# Control.net
KiCad netlist of a schematic drawn in EAGLE
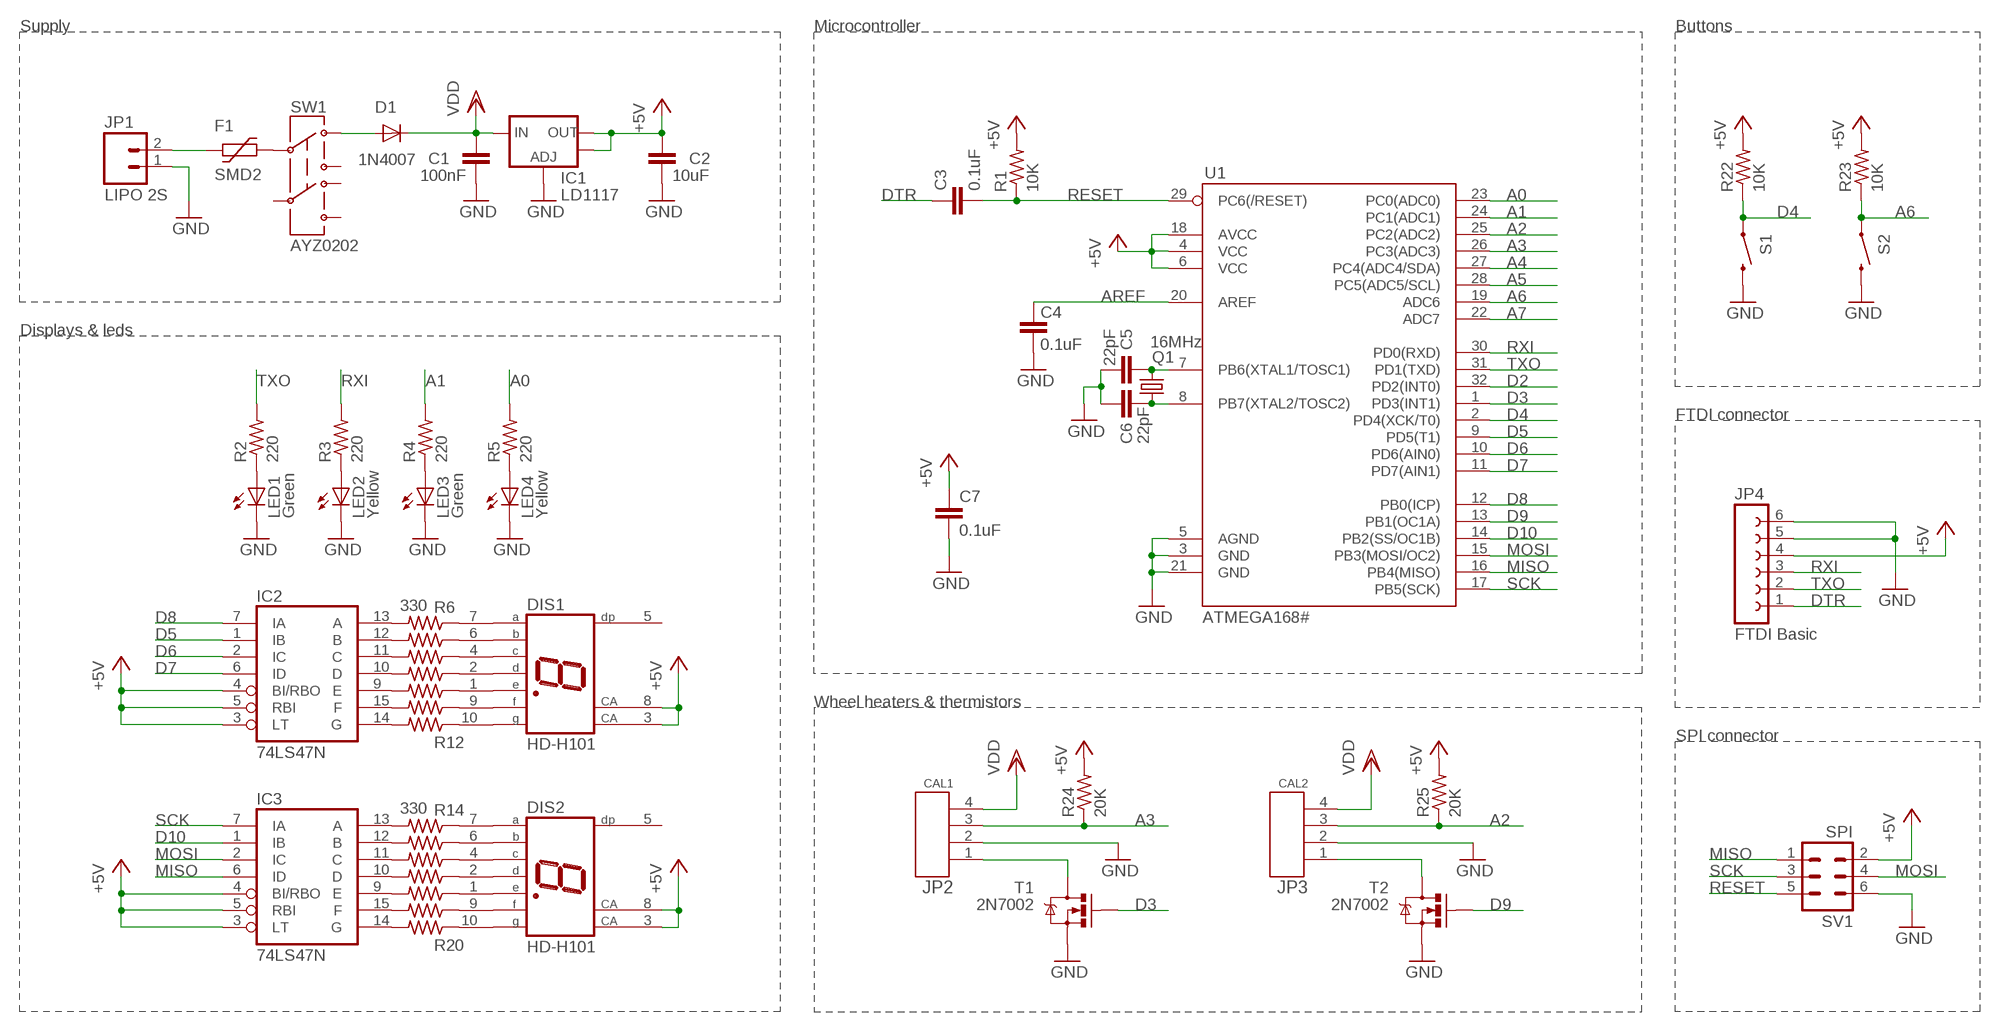
[diagram p0: schematic, sheet 1]

(export (version "E")
  (design (tool "Eeschema 10.0.6"))
  (components
    (comp (ref "C1")
      (value "100nF")
      (footprint "eagle-import:C0805")
      (libsource (lib "eagle-import") (part "C-EUC0805"))
    )
    (comp (ref "C2")
      (value "10uF")
      (footprint "eagle-import:C0805")
      (libsource (lib "eagle-import") (part "C-EUC0805"))
    )
    (comp (ref "C3")
      (value "0.1uF")
      (footprint "eagle-import:C0805")
      (libsource (lib "eagle-import") (part "C-EUC0805"))
    )
    (comp (ref "C4")
      (value "0.1uF")
      (footprint "eagle-import:C0805")
      (libsource (lib "eagle-import") (part "C-EUC0805"))
    )
    (comp (ref "C5")
      (value "22pF")
      (footprint "eagle-import:C0805")
      (libsource (lib "eagle-import") (part "C-EUC0805"))
    )
    (comp (ref "C6")
      (value "22pF")
      (footprint "eagle-import:C0805")
      (libsource (lib "eagle-import") (part "C-EUC0805"))
    )
    (comp (ref "C7")
      (value "0.1uF")
      (footprint "eagle-import:C0805")
      (libsource (lib "eagle-import") (part "C-EUC0805"))
    )
    (comp (ref "D1")
      (value "1N4007")
      (footprint "eagle-import:SOD106-R")
      (libsource (lib "eagle-import") (part "DIODE-SOD106-R"))
    )
    (comp (ref "DIS1")
      (value "HD-H101")
      (footprint "eagle-import:HDSP-M")
      (libsource (lib "eagle-import") (part "HD-H101"))
    )
    (comp (ref "DIS2")
      (value "HD-H101")
      (footprint "eagle-import:HDSP-M")
      (fields (field (name "OC_FARNELL") "unknown") (field (name "OC_NEWARK") "unknown"))
      (libsource (lib "eagle-import") (part "HD-H101"))
    )
    (comp (ref "F1")
      (value "SMD2")
      (footprint "eagle-import:SMD2")
      (libsource (lib "eagle-import") (part "SMD2"))
    )
    (comp (ref "IC1")
      (value "LD1117")
      (footprint "eagle-import:SOT223")
      (libsource (lib "eagle-import") (part "V_REG_LM1117SOT223"))
    )
    (comp (ref "IC2")
      (value "74LS47N")
      (footprint "eagle-import:DIL16")
      (libsource (lib "eagle-import") (part "7447NLS"))
    )
    (comp (ref "IC3")
      (value "74LS47N")
      (footprint "eagle-import:DIL16")
      (libsource (lib "eagle-import") (part "7447NLS"))
    )
    (comp (ref "JP1")
      (value "LIPO 2S")
      (footprint "eagle-import:1X02")
      (libsource (lib "eagle-import") (part "M02NG"))
    )
    (comp (ref "JP2")
      (value "CAL1")
      (footprint "eagle-import:4_PINES_MACHO_TUMBADOS")
      (libsource (lib "eagle-import") (part "4_PINES_RA"))
    )
    (comp (ref "JP3")
      (value "CAL2")
      (footprint "eagle-import:4_PINES_MACHO_TUMBADOS")
      (libsource (lib "eagle-import") (part "4_PINES_RA"))
    )
    (comp (ref "JP4")
      (value "FTDI Basic")
      (footprint "eagle-import:FE06W")
      (libsource (lib "eagle-import") (part "FE06W"))
    )
    (comp (ref "LED1")
      (value "Green")
      (footprint "eagle-import:LED3MM")
      (libsource (lib "eagle-import") (part "LED3MM"))
    )
    (comp (ref "LED2")
      (value "Yellow")
      (footprint "eagle-import:LED3MM")
      (libsource (lib "eagle-import") (part "LED3MM"))
    )
    (comp (ref "LED3")
      (value "Green")
      (footprint "eagle-import:LED3MM")
      (libsource (lib "eagle-import") (part "LED3MM"))
    )
    (comp (ref "LED4")
      (value "Yellow")
      (footprint "eagle-import:LED3MM")
      (libsource (lib "eagle-import") (part "LED3MM"))
    )
    (comp (ref "Q1")
      (value "16MHz")
      (footprint "eagle-import:HC49_S")
      (libsource (lib "eagle-import") (part "CRYSTALHC49S"))
    )
    (comp (ref "R1")
      (value "10K")
      (footprint "eagle-import:R0805")
      (libsource (lib "eagle-import") (part "R-US_R0805"))
    )
    (comp (ref "R2")
      (value "220")
      (footprint "eagle-import:R0805")
      (libsource (lib "eagle-import") (part "R-US_R0805"))
    )
    (comp (ref "R3")
      (value "220")
      (footprint "eagle-import:R0805")
      (libsource (lib "eagle-import") (part "R-US_R0805"))
    )
    (comp (ref "R4")
      (value "220")
      (footprint "eagle-import:R0805")
      (libsource (lib "eagle-import") (part "R-US_R0805"))
    )
    (comp (ref "R5")
      (value "220")
      (footprint "eagle-import:R0805")
      (libsource (lib "eagle-import") (part "R-US_R0805"))
    )
    (comp (ref "R6")
      (value "330")
      (footprint "eagle-import:R0805")
      (libsource (lib "eagle-import") (part "R-US_R0805"))
    )
    (comp (ref "R7")
      (value "330")
      (footprint "eagle-import:R0805")
      (libsource (lib "eagle-import") (part "R-US_R0805"))
    )
    (comp (ref "R8")
      (value "330")
      (footprint "eagle-import:R0805")
      (libsource (lib "eagle-import") (part "R-US_R0805"))
    )
    (comp (ref "R9")
      (value "330")
      (footprint "eagle-import:R0805")
      (libsource (lib "eagle-import") (part "R-US_R0805"))
    )
    (comp (ref "R10")
      (value "330")
      (footprint "eagle-import:R0805")
      (libsource (lib "eagle-import") (part "R-US_R0805"))
    )
    (comp (ref "R11")
      (value "330")
      (footprint "eagle-import:R0805")
      (libsource (lib "eagle-import") (part "R-US_R0805"))
    )
    (comp (ref "R12")
      (value "330")
      (footprint "eagle-import:R0805")
      (libsource (lib "eagle-import") (part "R-US_R0805"))
    )
    (comp (ref "R14")
      (value "330")
      (footprint "eagle-import:R0805")
      (libsource (lib "eagle-import") (part "R-US_R0805"))
    )
    (comp (ref "R15")
      (value "330")
      (footprint "eagle-import:R0805")
      (libsource (lib "eagle-import") (part "R-US_R0805"))
    )
    (comp (ref "R16")
      (value "330")
      (footprint "eagle-import:R0805")
      (libsource (lib "eagle-import") (part "R-US_R0805"))
    )
    (comp (ref "R17")
      (value "330")
      (footprint "eagle-import:R0805")
      (libsource (lib "eagle-import") (part "R-US_R0805"))
    )
    (comp (ref "R18")
      (value "330")
      (footprint "eagle-import:R0805")
      (libsource (lib "eagle-import") (part "R-US_R0805"))
    )
    (comp (ref "R19")
      (value "330")
      (footprint "eagle-import:R0805")
      (libsource (lib "eagle-import") (part "R-US_R0805"))
    )
    (comp (ref "R20")
      (value "330")
      (footprint "eagle-import:R0805")
      (libsource (lib "eagle-import") (part "R-US_R0805"))
    )
    (comp (ref "R22")
      (value "10K")
      (footprint "eagle-import:R0805")
      (libsource (lib "eagle-import") (part "R-US_R0805"))
    )
    (comp (ref "R23")
      (value "10K")
      (footprint "eagle-import:R0805")
      (libsource (lib "eagle-import") (part "R-US_R0805"))
    )
    (comp (ref "R24")
      (value "20K")
      (footprint "eagle-import:R0805")
      (libsource (lib "eagle-import") (part "R-US_R0805"))
    )
    (comp (ref "R25")
      (value "20K")
      (footprint "eagle-import:R0805")
      (libsource (lib "eagle-import") (part "R-US_R0805"))
    )
    (comp (ref "S1")
      (value "SWITCH-MOMENTARY-2PTH")
      (footprint "eagle-import:TACTILE-PTH")
      (libsource (lib "eagle-import") (part "SWITCH-MOMENTARY-2PTH"))
    )
    (comp (ref "S2")
      (value "SWITCH-MOMENTARY-2PTH")
      (footprint "eagle-import:TACTILE-PTH")
      (libsource (lib "eagle-import") (part "SWITCH-MOMENTARY-2PTH"))
    )
    (comp (ref "SV1")
      (value "SPI")
      (footprint "eagle-import:MA03-2")
      (libsource (lib "eagle-import") (part "MA03-2"))
    )
    (comp (ref "SW1")
      (value "AYZ0202")
      (footprint "eagle-import:AYZ0202")
      (libsource (lib "eagle-import") (part "AYZ0202"))
    )
    (comp (ref "T1")
      (value "2N7002")
      (footprint "eagle-import:SOT23-3")
      (libsource (lib "eagle-import") (part "MOSFET-NCHANNELSMD"))
    )
    (comp (ref "T2")
      (value "2N7002")
      (footprint "eagle-import:SOT23-3")
      (libsource (lib "eagle-import") (part "MOSFET-NCHANNELSMD"))
    )
    (comp (ref "U1")
      (value "ATMEGA168#")
      (footprint "eagle-import:TQFP32-08")
      (libsource (lib "eagle-import") (part "ATMEGA168"))
    )
  )
  (nets
    (net (code "1") (name "+5V") (class "Default")
      (node (ref "C2") (pin "1") (pinfunction "1_1") (pintype "passive"))
      (node (ref "C7") (pin "1") (pinfunction "1_1") (pintype "passive"))
      (node (ref "DIS1") (pin "3") (pinfunction "CA_3") (pintype "passive"))
      (node (ref "DIS1") (pin "8") (pinfunction "CA_8") (pintype "passive"))
      (node (ref "DIS2") (pin "3") (pinfunction "CA_3") (pintype "passive"))
      (node (ref "DIS2") (pin "8") (pinfunction "CA_8") (pintype "passive"))
      (node (ref "IC1") (pin "2") (pinfunction "OUT_2") (pintype "output"))
      (node (ref "IC1") (pin "4") (pinfunction "OUT_4") (pintype "output"))
      (node (ref "IC2") (pin "3") (pinfunction "LT_3") (pintype "input"))
      (node (ref "IC2") (pin "4") (pinfunction "BI/RBO_4") (pintype "input"))
      (node (ref "IC2") (pin "5") (pinfunction "RBI_5") (pintype "input"))
      (node (ref "IC3") (pin "3") (pinfunction "LT_3") (pintype "input"))
      (node (ref "IC3") (pin "4") (pinfunction "BI/RBO_4") (pintype "input"))
      (node (ref "IC3") (pin "5") (pinfunction "RBI_5") (pintype "input"))
      (node (ref "JP4") (pin "4") (pinfunction "4_4") (pintype "passive"))
      (node (ref "R1") (pin "2") (pinfunction "2_2") (pintype "passive"))
      (node (ref "R22") (pin "2") (pinfunction "2_2") (pintype "passive"))
      (node (ref "R23") (pin "2") (pinfunction "2_2") (pintype "passive"))
      (node (ref "R24") (pin "2") (pinfunction "2_2") (pintype "passive"))
      (node (ref "R25") (pin "2") (pinfunction "2_2") (pintype "passive"))
      (node (ref "SV1") (pin "2") (pinfunction "2_2") (pintype "passive"))
      (node (ref "U1") (pin "18") (pinfunction "AVCC_18") (pintype "bidirectional"))
      (node (ref "U1") (pin "4") (pinfunction "VCC_4") (pintype "bidirectional"))
      (node (ref "U1") (pin "6") (pinfunction "VCC_6") (pintype "bidirectional"))
    )
    (net (code "2") (name "/A0") (class "Default")
      (node (ref "R5") (pin "2") (pinfunction "2_2") (pintype "passive"))
      (node (ref "U1") (pin "23") (pinfunction "PC0(ADC0)_23") (pintype "bidirectional"))
    )
    (net (code "3") (name "/A1") (class "Default")
      (node (ref "R4") (pin "2") (pinfunction "2_2") (pintype "passive"))
      (node (ref "U1") (pin "24") (pinfunction "PC1(ADC1)_24") (pintype "bidirectional"))
    )
    (net (code "4") (name "/A2") (class "Default")
      (node (ref "JP3") (pin "3") (pinfunction "3_3") (pintype "bidirectional"))
      (node (ref "R25") (pin "1") (pinfunction "1_1") (pintype "passive"))
      (node (ref "U1") (pin "25") (pinfunction "PC2(ADC2)_25") (pintype "bidirectional"))
    )
    (net (code "5") (name "/A3") (class "Default")
      (node (ref "JP2") (pin "3") (pinfunction "3_3") (pintype "bidirectional"))
      (node (ref "R24") (pin "1") (pinfunction "1_1") (pintype "passive"))
      (node (ref "U1") (pin "26") (pinfunction "PC3(ADC3)_26") (pintype "bidirectional"))
    )
    (net (code "6") (name "/A4") (class "Default")
      (node (ref "U1") (pin "27") (pinfunction "PC4(ADC4/SDA)_27") (pintype "bidirectional"))
    )
    (net (code "7") (name "/A5") (class "Default")
      (node (ref "U1") (pin "28") (pinfunction "PC5(ADC5/SCL)_28") (pintype "bidirectional"))
    )
    (net (code "8") (name "/A6") (class "Default")
      (node (ref "R23") (pin "1") (pinfunction "1_1") (pintype "passive"))
      (node (ref "S2") (pin "1") (pinfunction "1_1") (pintype "passive"))
      (node (ref "U1") (pin "19") (pinfunction "ADC6_19") (pintype "bidirectional"))
    )
    (net (code "9") (name "/A7") (class "Default")
      (node (ref "U1") (pin "22") (pinfunction "ADC7_22") (pintype "bidirectional"))
    )
    (net (code "10") (name "/AREF") (class "Default")
      (node (ref "C4") (pin "2") (pinfunction "2_2") (pintype "passive"))
      (node (ref "U1") (pin "20") (pinfunction "AREF_20") (pintype "bidirectional"))
    )
    (net (code "11") (name "/D2") (class "Default")
      (node (ref "U1") (pin "32") (pinfunction "PD2(INT0)_32") (pintype "bidirectional"))
    )
    (net (code "12") (name "/D3") (class "Default")
      (node (ref "T1") (pin "1") (pinfunction "G_1") (pintype "passive"))
      (node (ref "U1") (pin "1") (pinfunction "PD3(INT1)_1") (pintype "bidirectional"))
    )
    (net (code "13") (name "/D4") (class "Default")
      (node (ref "R22") (pin "1") (pinfunction "1_1") (pintype "passive"))
      (node (ref "S1") (pin "1") (pinfunction "1_1") (pintype "passive"))
      (node (ref "U1") (pin "2") (pinfunction "PD4(XCK/T0)_2") (pintype "bidirectional"))
    )
    (net (code "14") (name "/D5") (class "Default")
      (node (ref "IC2") (pin "1") (pinfunction "IB_1") (pintype "input"))
      (node (ref "U1") (pin "9") (pinfunction "PD5(T1)_9") (pintype "bidirectional"))
    )
    (net (code "15") (name "/D6") (class "Default")
      (node (ref "IC2") (pin "2") (pinfunction "IC_2") (pintype "input"))
      (node (ref "U1") (pin "10") (pinfunction "PD6(AIN0)_10") (pintype "bidirectional"))
    )
    (net (code "16") (name "/D7") (class "Default")
      (node (ref "IC2") (pin "6") (pinfunction "ID_6") (pintype "input"))
      (node (ref "U1") (pin "11") (pinfunction "PD7(AIN1)_11") (pintype "bidirectional"))
    )
    (net (code "17") (name "/D8") (class "Default")
      (node (ref "IC2") (pin "7") (pinfunction "IA_7") (pintype "input"))
      (node (ref "U1") (pin "12") (pinfunction "PB0(ICP)_12") (pintype "bidirectional"))
    )
    (net (code "18") (name "/D9") (class "Default")
      (node (ref "T2") (pin "1") (pinfunction "G_1") (pintype "passive"))
      (node (ref "U1") (pin "13") (pinfunction "PB1(OC1A)_13") (pintype "bidirectional"))
    )
    (net (code "19") (name "/D10") (class "Default")
      (node (ref "IC3") (pin "1") (pinfunction "IB_1") (pintype "input"))
      (node (ref "U1") (pin "14") (pinfunction "PB2(SS/OC1B)_14") (pintype "bidirectional"))
    )
    (net (code "20") (name "/DTR") (class "Default")
      (node (ref "C3") (pin "1") (pinfunction "1_1") (pintype "passive"))
      (node (ref "JP4") (pin "1") (pinfunction "1_1") (pintype "passive"))
    )
    (net (code "21") (name "/MISO") (class "Default")
      (node (ref "IC3") (pin "6") (pinfunction "ID_6") (pintype "input"))
      (node (ref "SV1") (pin "1") (pinfunction "1_1") (pintype "passive"))
      (node (ref "U1") (pin "16") (pinfunction "PB4(MISO)_16") (pintype "bidirectional"))
    )
    (net (code "22") (name "/MOSI") (class "Default")
      (node (ref "IC3") (pin "2") (pinfunction "IC_2") (pintype "input"))
      (node (ref "SV1") (pin "4") (pinfunction "4_4") (pintype "passive"))
      (node (ref "U1") (pin "15") (pinfunction "PB3(MOSI/OC2)_15") (pintype "bidirectional"))
    )
    (net (code "23") (name "/RESET") (class "Default")
      (node (ref "C3") (pin "2") (pinfunction "2_2") (pintype "passive"))
      (node (ref "R1") (pin "1") (pinfunction "1_1") (pintype "passive"))
      (node (ref "SV1") (pin "5") (pinfunction "5_5") (pintype "passive"))
      (node (ref "U1") (pin "29") (pinfunction "PC6(/RESET)_29") (pintype "bidirectional"))
    )
    (net (code "24") (name "/RXI") (class "Default")
      (node (ref "JP4") (pin "3") (pinfunction "3_3") (pintype "passive"))
      (node (ref "R3") (pin "2") (pinfunction "2_2") (pintype "passive"))
      (node (ref "U1") (pin "30") (pinfunction "PD0(RXD)_30") (pintype "bidirectional"))
    )
    (net (code "25") (name "/SCK") (class "Default")
      (node (ref "IC3") (pin "7") (pinfunction "IA_7") (pintype "input"))
      (node (ref "SV1") (pin "3") (pinfunction "3_3") (pintype "passive"))
      (node (ref "U1") (pin "17") (pinfunction "PB5(SCK)_17") (pintype "bidirectional"))
    )
    (net (code "26") (name "/TXO") (class "Default")
      (node (ref "JP4") (pin "2") (pinfunction "2_2") (pintype "passive"))
      (node (ref "R2") (pin "2") (pinfunction "2_2") (pintype "passive"))
      (node (ref "U1") (pin "31") (pinfunction "PD1(TXD)_31") (pintype "bidirectional"))
    )
    (net (code "27") (name "GND") (class "Default")
      (node (ref "C1") (pin "1") (pinfunction "1_1") (pintype "passive"))
      (node (ref "C2") (pin "2") (pinfunction "2_2") (pintype "passive"))
      (node (ref "C4") (pin "1") (pinfunction "1_1") (pintype "passive"))
      (node (ref "C5") (pin "1") (pinfunction "1_1") (pintype "passive"))
      (node (ref "C6") (pin "1") (pinfunction "1_1") (pintype "passive"))
      (node (ref "C7") (pin "2") (pinfunction "2_2") (pintype "passive"))
      (node (ref "IC1") (pin "1") (pinfunction "ADJ_1") (pintype "input"))
      (node (ref "JP1") (pin "1") (pinfunction "1_1") (pintype "passive"))
      (node (ref "JP2") (pin "2") (pinfunction "2_2") (pintype "bidirectional"))
      (node (ref "JP3") (pin "2") (pinfunction "2_2") (pintype "bidirectional"))
      (node (ref "JP4") (pin "5") (pinfunction "5_5") (pintype "passive"))
      (node (ref "JP4") (pin "6") (pinfunction "6_6") (pintype "passive"))
      (node (ref "LED1") (pin "K") (pinfunction "C_K") (pintype "passive"))
      (node (ref "LED2") (pin "K") (pinfunction "C_K") (pintype "passive"))
      (node (ref "LED3") (pin "K") (pinfunction "C_K") (pintype "passive"))
      (node (ref "LED4") (pin "K") (pinfunction "C_K") (pintype "passive"))
      (node (ref "S1") (pin "3") (pinfunction "2_3") (pintype "passive"))
      (node (ref "S2") (pin "3") (pinfunction "2_3") (pintype "passive"))
      (node (ref "SV1") (pin "6") (pinfunction "6_6") (pintype "passive"))
      (node (ref "T1") (pin "2") (pinfunction "S_2") (pintype "passive"))
      (node (ref "T2") (pin "2") (pinfunction "S_2") (pintype "passive"))
      (node (ref "U1") (pin "21") (pinfunction "GND_21") (pintype "bidirectional"))
      (node (ref "U1") (pin "3") (pinfunction "GND_3") (pintype "bidirectional"))
      (node (ref "U1") (pin "5") (pinfunction "AGND_5") (pintype "bidirectional"))
    )
    (net (code "28") (name "Net-(DIS1-A)") (class "Default")
      (node (ref "DIS1") (pin "7") (pinfunction "A_7") (pintype "passive"))
      (node (ref "R6") (pin "1") (pinfunction "1_1") (pintype "passive"))
    )
    (net (code "29") (name "Net-(DIS1-B)") (class "Default")
      (node (ref "DIS1") (pin "6") (pinfunction "B_6") (pintype "passive"))
      (node (ref "R7") (pin "1") (pinfunction "1_1") (pintype "passive"))
    )
    (net (code "30") (name "Net-(DIS1-C)") (class "Default")
      (node (ref "DIS1") (pin "4") (pinfunction "C_4") (pintype "passive"))
      (node (ref "R8") (pin "1") (pinfunction "1_1") (pintype "passive"))
    )
    (net (code "31") (name "Net-(DIS1-D)") (class "Default")
      (node (ref "DIS1") (pin "2") (pinfunction "D_2") (pintype "passive"))
      (node (ref "R9") (pin "1") (pinfunction "1_1") (pintype "passive"))
    )
    (net (code "32") (name "Net-(DIS1-E)") (class "Default")
      (node (ref "DIS1") (pin "1") (pinfunction "E_1") (pintype "passive"))
      (node (ref "R10") (pin "1") (pinfunction "1_1") (pintype "passive"))
    )
    (net (code "33") (name "Net-(DIS1-F)") (class "Default")
      (node (ref "DIS1") (pin "9") (pinfunction "F_9") (pintype "passive"))
      (node (ref "R11") (pin "1") (pinfunction "1_1") (pintype "passive"))
    )
    (net (code "34") (name "Net-(DIS1-G)") (class "Default")
      (node (ref "DIS1") (pin "10") (pinfunction "G_10") (pintype "passive"))
      (node (ref "R12") (pin "1") (pinfunction "1_1") (pintype "passive"))
    )
    (net (code "35") (name "Net-(DIS2-A)") (class "Default")
      (node (ref "DIS2") (pin "7") (pinfunction "A_7") (pintype "passive"))
      (node (ref "R14") (pin "1") (pinfunction "1_1") (pintype "passive"))
    )
    (net (code "36") (name "Net-(DIS2-B)") (class "Default")
      (node (ref "DIS2") (pin "6") (pinfunction "B_6") (pintype "passive"))
      (node (ref "R15") (pin "1") (pinfunction "1_1") (pintype "passive"))
    )
    (net (code "37") (name "Net-(DIS2-C)") (class "Default")
      (node (ref "DIS2") (pin "4") (pinfunction "C_4") (pintype "passive"))
      (node (ref "R16") (pin "1") (pinfunction "1_1") (pintype "passive"))
    )
    (net (code "38") (name "Net-(DIS2-D)") (class "Default")
      (node (ref "DIS2") (pin "2") (pinfunction "D_2") (pintype "passive"))
      (node (ref "R17") (pin "1") (pinfunction "1_1") (pintype "passive"))
    )
    (net (code "39") (name "Net-(DIS2-E)") (class "Default")
      (node (ref "DIS2") (pin "1") (pinfunction "E_1") (pintype "passive"))
      (node (ref "R18") (pin "1") (pinfunction "1_1") (pintype "passive"))
    )
    (net (code "40") (name "Net-(DIS2-F)") (class "Default")
      (node (ref "DIS2") (pin "9") (pinfunction "F_9") (pintype "passive"))
      (node (ref "R19") (pin "1") (pinfunction "1_1") (pintype "passive"))
    )
    (net (code "41") (name "Net-(DIS2-G)") (class "Default")
      (node (ref "DIS2") (pin "10") (pinfunction "G_10") (pintype "passive"))
      (node (ref "R20") (pin "1") (pinfunction "1_1") (pintype "passive"))
    )
    (net (code "42") (name "Net-(F1-1)") (class "Default")
      (node (ref "F1") (pin "P$1") (pinfunction "1_P$1") (pintype "passive"))
      (node (ref "JP1") (pin "2") (pinfunction "2_2") (pintype "passive"))
    )
    (net (code "43") (name "Net-(F1-2)") (class "Default")
      (node (ref "F1") (pin "P$2") (pinfunction "2_P$2") (pintype "passive"))
      (node (ref "SW1") (pin "2") (pinfunction "2_2") (pintype "bidirectional"))
    )
    (net (code "44") (name "Net-(IC2A-A)") (class "Default")
      (node (ref "IC2") (pin "13") (pinfunction "A_13") (pintype "output"))
      (node (ref "R6") (pin "2") (pinfunction "2_2") (pintype "passive"))
    )
    (net (code "45") (name "Net-(IC2A-B)") (class "Default")
      (node (ref "IC2") (pin "12") (pinfunction "B_12") (pintype "output"))
      (node (ref "R7") (pin "2") (pinfunction "2_2") (pintype "passive"))
    )
    (net (code "46") (name "Net-(IC2A-C)") (class "Default")
      (node (ref "IC2") (pin "11") (pinfunction "C_11") (pintype "output"))
      (node (ref "R8") (pin "2") (pinfunction "2_2") (pintype "passive"))
    )
    (net (code "47") (name "Net-(IC2A-D)") (class "Default")
      (node (ref "IC2") (pin "10") (pinfunction "D_10") (pintype "output"))
      (node (ref "R9") (pin "2") (pinfunction "2_2") (pintype "passive"))
    )
    (net (code "48") (name "Net-(IC2A-E)") (class "Default")
      (node (ref "IC2") (pin "9") (pinfunction "E_9") (pintype "output"))
      (node (ref "R10") (pin "2") (pinfunction "2_2") (pintype "passive"))
    )
    (net (code "49") (name "Net-(IC2A-F)") (class "Default")
      (node (ref "IC2") (pin "15") (pinfunction "F_15") (pintype "output"))
      (node (ref "R11") (pin "2") (pinfunction "2_2") (pintype "passive"))
    )
    (net (code "50") (name "Net-(IC2A-G)") (class "Default")
      (node (ref "IC2") (pin "14") (pinfunction "G_14") (pintype "output"))
      (node (ref "R12") (pin "2") (pinfunction "2_2") (pintype "passive"))
    )
    (net (code "51") (name "Net-(IC3A-A)") (class "Default")
      (node (ref "IC3") (pin "13") (pinfunction "A_13") (pintype "output"))
      (node (ref "R14") (pin "2") (pinfunction "2_2") (pintype "passive"))
    )
    (net (code "52") (name "Net-(IC3A-B)") (class "Default")
      (node (ref "IC3") (pin "12") (pinfunction "B_12") (pintype "output"))
      (node (ref "R15") (pin "2") (pinfunction "2_2") (pintype "passive"))
    )
    (net (code "53") (name "Net-(IC3A-C)") (class "Default")
      (node (ref "IC3") (pin "11") (pinfunction "C_11") (pintype "output"))
      (node (ref "R16") (pin "2") (pinfunction "2_2") (pintype "passive"))
    )
    (net (code "54") (name "Net-(IC3A-D)") (class "Default")
      (node (ref "IC3") (pin "10") (pinfunction "D_10") (pintype "output"))
      (node (ref "R17") (pin "2") (pinfunction "2_2") (pintype "passive"))
    )
    (net (code "55") (name "Net-(IC3A-E)") (class "Default")
      (node (ref "IC3") (pin "9") (pinfunction "E_9") (pintype "output"))
      (node (ref "R18") (pin "2") (pinfunction "2_2") (pintype "passive"))
    )
    (net (code "56") (name "Net-(IC3A-F)") (class "Default")
      (node (ref "IC3") (pin "15") (pinfunction "F_15") (pintype "output"))
      (node (ref "R19") (pin "2") (pinfunction "2_2") (pintype "passive"))
    )
    (net (code "57") (name "Net-(IC3A-G)") (class "Default")
      (node (ref "IC3") (pin "14") (pinfunction "G_14") (pintype "output"))
      (node (ref "R20") (pin "2") (pinfunction "2_2") (pintype "passive"))
    )
    (net (code "58") (name "Net-(LED1-PadA)") (class "Default")
      (node (ref "LED1") (pin "A") (pinfunction "A_A") (pintype "passive"))
      (node (ref "R2") (pin "1") (pinfunction "1_1") (pintype "passive"))
    )
    (net (code "59") (name "Net-(LED2-PadA)") (class "Default")
      (node (ref "LED2") (pin "A") (pinfunction "A_A") (pintype "passive"))
      (node (ref "R3") (pin "1") (pinfunction "1_1") (pintype "passive"))
    )
    (net (code "60") (name "Net-(LED3-PadA)") (class "Default")
      (node (ref "LED3") (pin "A") (pinfunction "A_A") (pintype "passive"))
      (node (ref "R4") (pin "1") (pinfunction "1_1") (pintype "passive"))
    )
    (net (code "61") (name "Net-(LED4-PadA)") (class "Default")
      (node (ref "LED4") (pin "A") (pinfunction "A_A") (pintype "passive"))
      (node (ref "R5") (pin "1") (pinfunction "1_1") (pintype "passive"))
    )
    (net (code "62") (name "Net-(SW1-1)") (class "Default")
      (node (ref "D1") (pin "A") (pinfunction "A_A") (pintype "passive"))
      (node (ref "SW1") (pin "3") (pinfunction "1_3") (pintype "bidirectional"))
    )
    (net (code "63") (name "Net-(T1-D)") (class "Default")
      (node (ref "JP2") (pin "1") (pinfunction "1_1") (pintype "bidirectional"))
      (node (ref "T1") (pin "3") (pinfunction "D_3") (pintype "passive"))
    )
    (net (code "64") (name "Net-(T2-D)") (class "Default")
      (node (ref "JP3") (pin "1") (pinfunction "1_1") (pintype "bidirectional"))
      (node (ref "T2") (pin "3") (pinfunction "D_3") (pintype "passive"))
    )
    (net (code "65") (name "Net-(U1-PB6(XTAL1{slash}TOSC1))") (class "Default")
      (node (ref "C5") (pin "2") (pinfunction "2_2") (pintype "passive"))
      (node (ref "Q1") (pin "1") (pinfunction "1_1") (pintype "passive"))
      (node (ref "U1") (pin "7") (pinfunction "PB6(XTAL1/TOSC1)_7") (pintype "bidirectional"))
    )
    (net (code "66") (name "Net-(U1-PB7(XTAL2{slash}TOSC2))") (class "Default")
      (node (ref "C6") (pin "2") (pinfunction "2_2") (pintype "passive"))
      (node (ref "Q1") (pin "2") (pinfunction "2_2") (pintype "passive"))
      (node (ref "U1") (pin "8") (pinfunction "PB7(XTAL2/TOSC2)_8") (pintype "bidirectional"))
    )
    (net (code "67") (name "VDD") (class "Default")
      (node (ref "C1") (pin "2") (pinfunction "2_2") (pintype "passive"))
      (node (ref "D1") (pin "C") (pinfunction "C_C") (pintype "passive"))
      (node (ref "IC1") (pin "3") (pinfunction "IN_3") (pintype "input"))
      (node (ref "JP2") (pin "4") (pinfunction "4_4") (pintype "bidirectional"))
      (node (ref "JP3") (pin "4") (pinfunction "4_4") (pintype "bidirectional"))
    )
    (net (code "68") (name "unconnected-(DIS1-DP-Pad5)") (class "Default")
      (node (ref "DIS1") (pin "5") (pinfunction "DP_5") (pintype "passive"))
    )
    (net (code "69") (name "unconnected-(DIS2-DP-Pad5)") (class "Default")
      (node (ref "DIS2") (pin "5") (pinfunction "DP_5") (pintype "passive"))
    )
    (net (code "70") (name "unconnected-(SW1-3-Pad1)") (class "Default")
      (node (ref "SW1") (pin "1") (pinfunction "3_1") (pintype "bidirectional"))
    )
    (net (code "71") (name "unconnected-(SW1-4-Pad6)") (class "Default")
      (node (ref "SW1") (pin "6") (pinfunction "4_6") (pintype "bidirectional"))
    )
    (net (code "72") (name "unconnected-(SW1-6-Pad4)") (class "Default")
      (node (ref "SW1") (pin "4") (pinfunction "6_4") (pintype "bidirectional"))
    )
    (net (code "73") (name "unconnected-(SW1-Pad5)") (class "Default")
      (node (ref "SW1") (pin "5") (pinfunction "5_5") (pintype "bidirectional"))
    )
  )
)
